# 2.net
KiCad netlist of a schematic drawn in Altium Designer
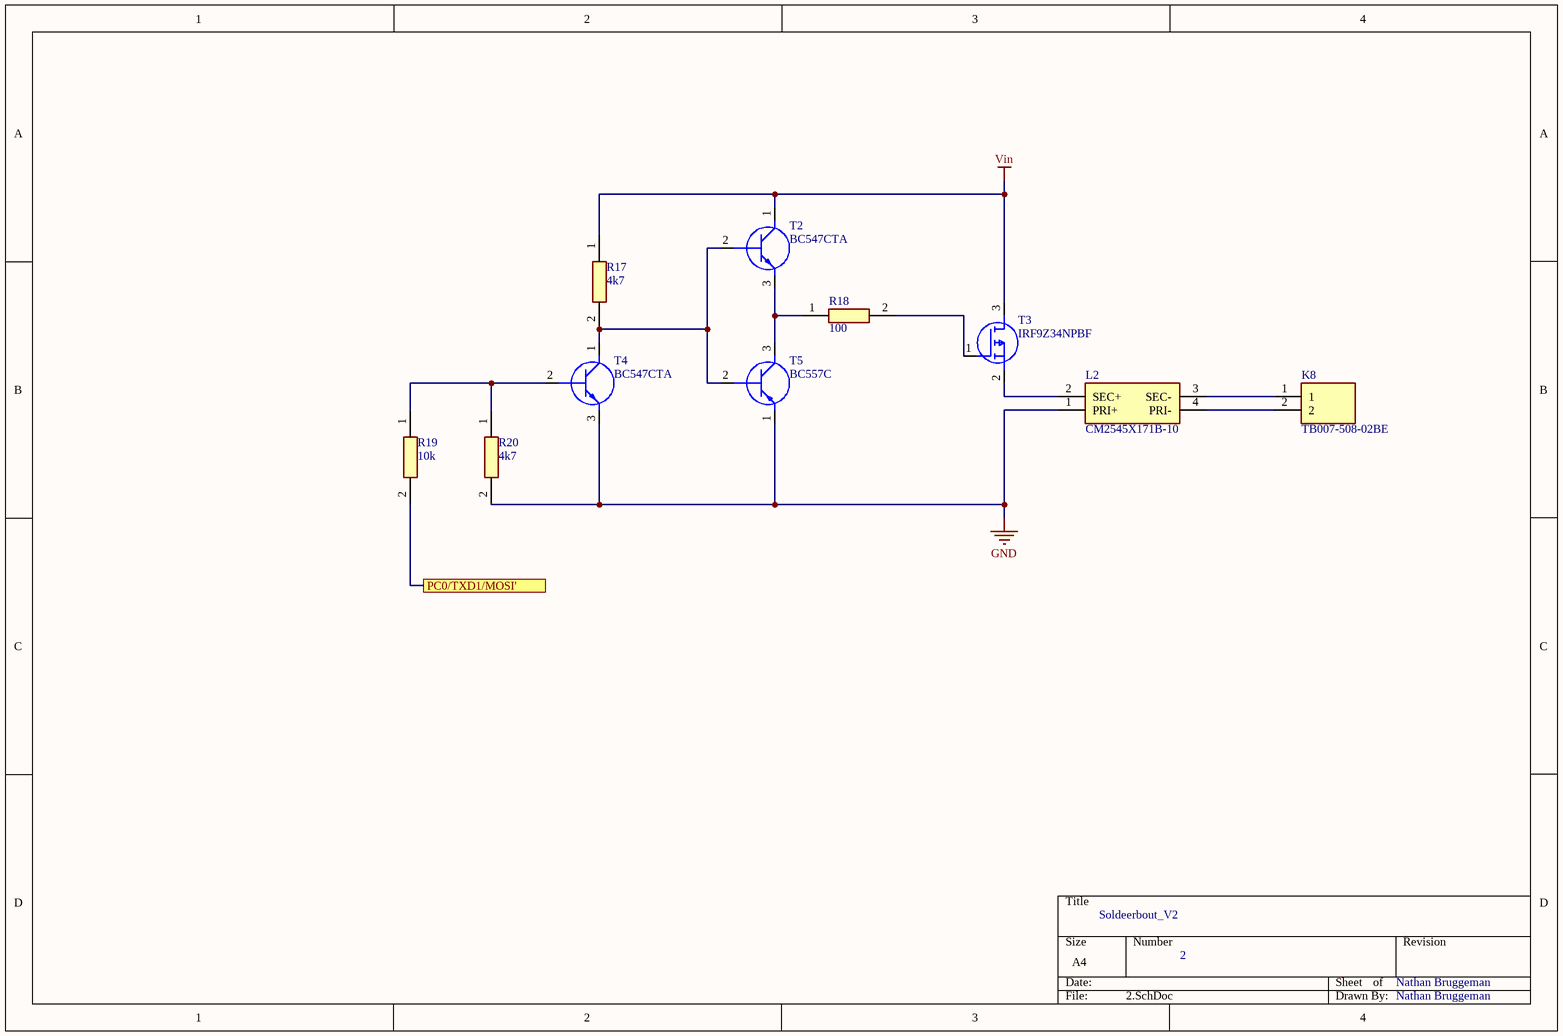
[diagram p0: 2.SchDoc]

(export (version "E")
  (design (tool "Eeschema 10.0.6"))
  (components
    (comp (ref "K8")
      (value "TB007-508-02BE")
      (footprint "TB00750802BE")
      (description "Connector")
      (fields (field (name "MOUSER2 PART NUMBER") "490-TB007-508-02BE"))
      (libsource (lib "K1_K2_K3_K8") (part "TB007-508-02BE"))
    )
    (comp (ref "L2")
      (value "CM2545X171B-10")
      (footprint "CM2545X171B10")
      (description "Transformer")
      (libsource (lib "L2") (part "CM2545X171B-10"))
    )
    (comp (ref "R17")
      (value "4k7")
      (footprint "0805")
      (description "Resistor")
      (fields (field (name "MANUFACTURER_PART_NUMBER") "CFN0805-FZ-R030ELF"))
      (libsource (lib "Weerstand_0805") (part "CFN0805-FZ-R030ELF"))
    )
    (comp (ref "R18")
      (value "100")
      (footprint "0805")
      (description "Resistor")
      (fields (field (name "MANUFACTURER_PART_NUMBER") "CFN0805-FZ-R030ELF"))
      (libsource (lib "") (part "CFN0805-FZ-R030ELF_1"))
    )
    (comp (ref "R19")
      (value "10k")
      (footprint "0805")
      (description "Resistor")
      (fields (field (name "MANUFACTURER_PART_NUMBER") "CFN0805-FZ-R030ELF"))
      (libsource (lib "Weerstand_0805") (part "CFN0805-FZ-R030ELF"))
    )
    (comp (ref "R20")
      (value "4k7")
      (footprint "0805")
      (description "Resistor")
      (fields (field (name "MANUFACTURER_PART_NUMBER") "CFN0805-FZ-R030ELF"))
      (libsource (lib "Weerstand_0805") (part "CFN0805-FZ-R030ELF"))
    )
    (comp (ref "T2")
      (value "BC547CTA")
      (footprint "BC557C")
      (description "Transistor BJT NPN")
      (libsource (lib "T1_T2_T4") (part "BC547CTA"))
    )
    (comp (ref "T3")
      (value "IRF9Z34NPBF")
      (footprint "TO254P469X1042X1967-3P")
      (description "MOSFET (P-Channel)")
      (fields (field (name "MOUSER2 PART NUMBER") "942-IRF9Z34NPBF"))
      (libsource (lib "T3") (part "IRF9Z34NPBF"))
    )
    (comp (ref "T4")
      (value "BC547CTA")
      (footprint "BC557C")
      (description "Transistor BJT NPN")
      (libsource (lib "T1_T2_T4") (part "BC547CTA"))
    )
    (comp (ref "T5")
      (value "BC557C")
      (footprint "BC557C")
      (description "Transistor BJT PNP")
      (libsource (lib "T5") (part "BC557C"))
    )
  )
  (nets
    (net (code "1") (name "/PC0{slash}TXD1{slash}MOSI'") (class "Default")
      (node (ref "R19") (pin "2") (pinfunction "2_2") (pintype "passive"))
    )
    (net (code "2") (name "GND") (class "Default")
      (node (ref "L2") (pin "1") (pinfunction "PRI+_1") (pintype "passive"))
      (node (ref "R20") (pin "2") (pinfunction "2_2") (pintype "passive"))
      (node (ref "T4") (pin "3") (pinfunction "E_3") (pintype "passive"))
      (node (ref "T5") (pin "1") (pinfunction "E_1") (pintype "passive"))
    )
    (net (code "3") (name "Net-(L2-PRI-)") (class "Default")
      (node (ref "K8") (pin "2") (pinfunction "2_2") (pintype "passive"))
      (node (ref "L2") (pin "4") (pinfunction "PRI-_4") (pintype "passive"))
    )
    (net (code "4") (name "Net-(L2-SEC+)") (class "Default")
      (node (ref "L2") (pin "2") (pinfunction "SEC+_2") (pintype "passive"))
      (node (ref "T3") (pin "2") (pinfunction "S_2") (pintype "passive"))
    )
    (net (code "5") (name "Net-(L2-SEC-)") (class "Default")
      (node (ref "K8") (pin "1") (pinfunction "1_1") (pintype "passive"))
      (node (ref "L2") (pin "3") (pinfunction "SEC-_3") (pintype "passive"))
    )
    (net (code "6") (name "Net-(T2-B)") (class "Default")
      (node (ref "R17") (pin "2") (pinfunction "2_2") (pintype "passive"))
      (node (ref "T2") (pin "2") (pinfunction "B_2") (pintype "passive"))
      (node (ref "T4") (pin "1") (pinfunction "C_1") (pintype "passive"))
      (node (ref "T5") (pin "2") (pinfunction "B_2") (pintype "passive"))
    )
    (net (code "7") (name "Net-(T2-E)") (class "Default")
      (node (ref "R18") (pin "1") (pinfunction "1_1") (pintype "passive"))
      (node (ref "T2") (pin "3") (pinfunction "E_3") (pintype "passive"))
      (node (ref "T5") (pin "3") (pinfunction "C_3") (pintype "passive"))
    )
    (net (code "8") (name "Net-(T3-G)") (class "Default")
      (node (ref "R18") (pin "2") (pinfunction "2_2") (pintype "passive"))
      (node (ref "T3") (pin "1") (pinfunction "G_1") (pintype "passive"))
    )
    (net (code "9") (name "Net-(T4-B)") (class "Default")
      (node (ref "R19") (pin "1") (pinfunction "1_1") (pintype "passive"))
      (node (ref "R20") (pin "1") (pinfunction "1_1") (pintype "passive"))
      (node (ref "T4") (pin "2") (pinfunction "B_2") (pintype "passive"))
    )
    (net (code "10") (name "Vin") (class "Default")
      (node (ref "R17") (pin "1") (pinfunction "1_1") (pintype "passive"))
      (node (ref "T2") (pin "1") (pinfunction "C_1") (pintype "passive"))
      (node (ref "T3") (pin "3") (pinfunction "D_3") (pintype "passive"))
    )
  )
)
